# 2_POWER.net
KiCad netlist of a schematic drawn in Altium Designer
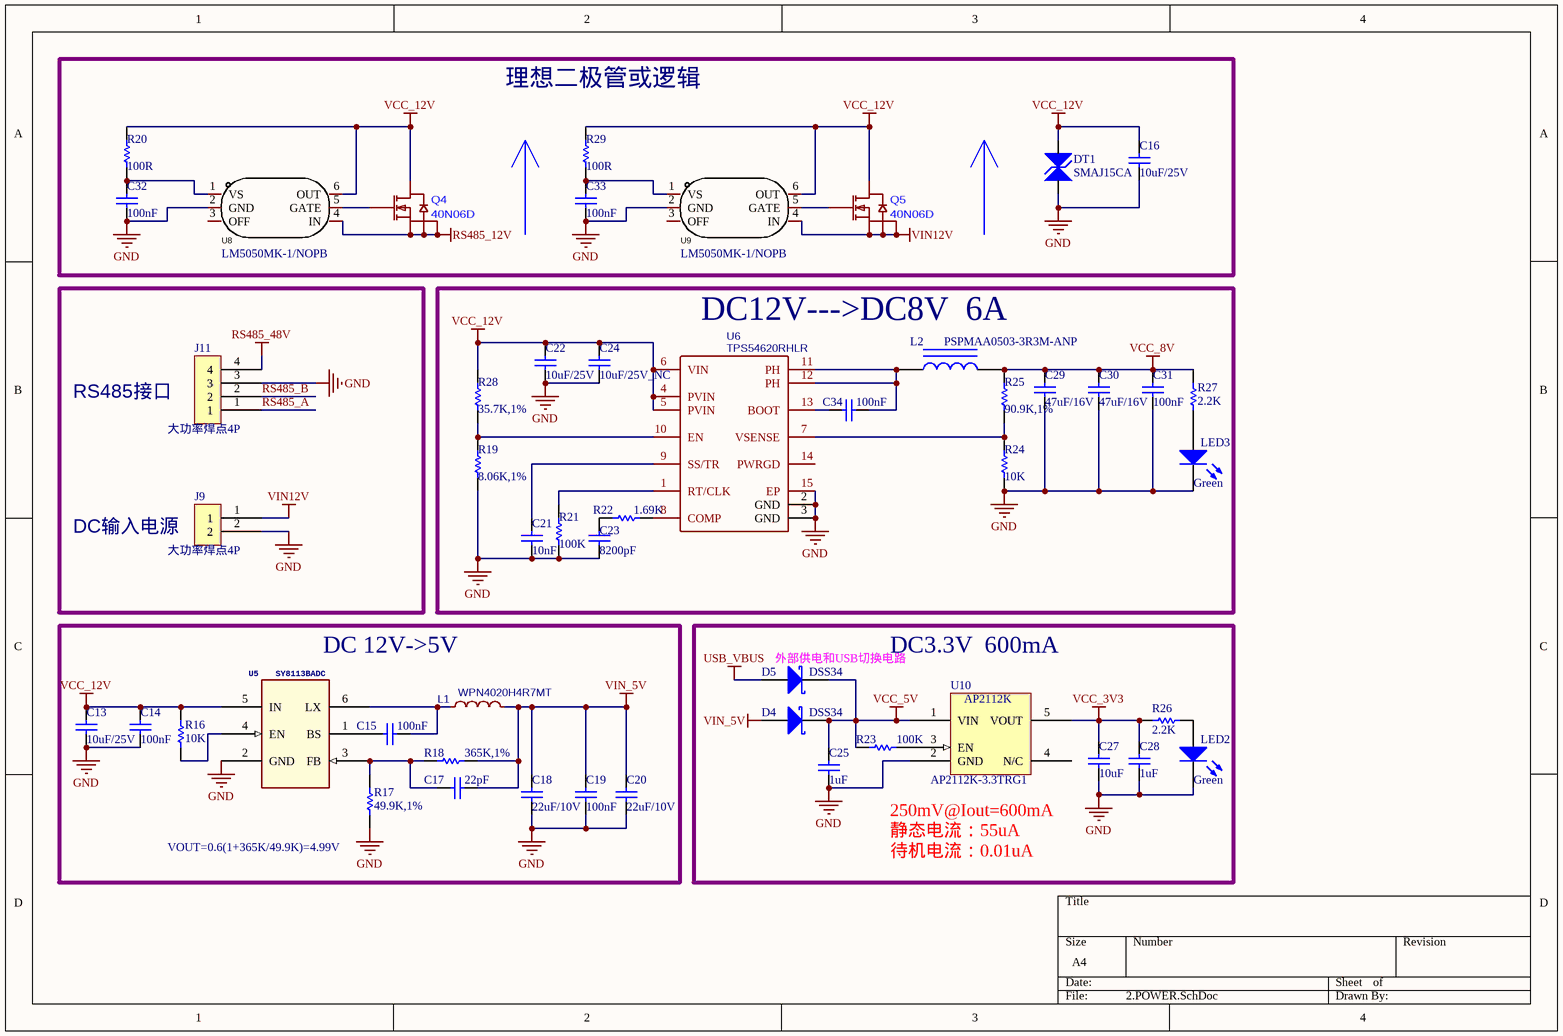
[diagram p0: 2.POWER.SchDoc]

(export (version "E")
  (design (tool "Eeschema 10.0.6"))
  (components
    (comp (ref "C13")
      (value "10uF/25V")
      (footprint "0805C")
      (description "Capacitor")
      (fields (field (name "PARTNUMBER") "CAP100NF") (field (name "PUBLISHER") "Altium Limited"))
      (libsource (lib "Miscellaneous Devices") (part "Cap"))
    )
    (comp (ref "C14")
      (value "100nF")
      (footprint "0402")
      (description "Capacitor")
      (fields (field (name "PARTNUMBER") "CAP100NF") (field (name "PUBLISHER") "Altium Limited"))
      (libsource (lib "Miscellaneous Devices") (part "Cap"))
    )
    (comp (ref "C15")
      (value "100nF")
      (footprint "0402")
      (description "Capacitor")
      (fields (field (name "PARTNUMBER") "CAP100NF") (field (name "PUBLISHER") "Altium Limited"))
      (libsource (lib "Miscellaneous Devices") (part "Cap"))
    )
    (comp (ref "C16")
      (value "10uF/25V")
      (footprint "0805C")
      (description "Capacitor")
      (fields (field (name "PARTNUMBER") "CAP100NF") (field (name "PUBLISHER") "Altium Limited"))
      (libsource (lib "Miscellaneous Devices") (part "Cap"))
    )
    (comp (ref "C17")
      (value "22pF")
      (footprint "0402")
      (description "Capacitor")
      (fields (field (name "PARTNUMBER") "CAP100NF") (field (name "PUBLISHER") "Altium Limited"))
      (libsource (lib "Miscellaneous Devices") (part "Cap"))
    )
    (comp (ref "C18")
      (value "22uF/10V")
      (footprint "0603")
      (description "Capacitor")
      (fields (field (name "PARTNUMBER") "CAP100NF") (field (name "PUBLISHER") "Altium Limited"))
      (libsource (lib "Miscellaneous Devices") (part "Cap"))
    )
    (comp (ref "C19")
      (value "100nF")
      (footprint "0402")
      (description "Capacitor")
      (fields (field (name "PARTNUMBER") "CAP100NF") (field (name "PUBLISHER") "Altium Limited"))
      (libsource (lib "Miscellaneous Devices") (part "Cap"))
    )
    (comp (ref "C20")
      (value "22uF/10V")
      (footprint "0603")
      (description "Capacitor")
      (fields (field (name "PARTNUMBER") "CAP100NF") (field (name "PUBLISHER") "Altium Limited"))
      (libsource (lib "Miscellaneous Devices") (part "Cap"))
    )
    (comp (ref "C21")
      (value "10nF")
      (footprint "0402")
      (description "Capacitor")
      (fields (field (name "PARTNUMBER") "CAP100NF") (field (name "PUBLISHER") "Altium Limited"))
      (libsource (lib "Miscellaneous Devices") (part "Cap"))
    )
    (comp (ref "C22")
      (value "10uF/25V")
      (footprint "0805C")
      (description "Capacitor")
      (fields (field (name "PARTNUMBER") "CAP100NF") (field (name "PUBLISHER") "Altium Limited"))
      (libsource (lib "Miscellaneous Devices") (part "Cap"))
    )
    (comp (ref "C23")
      (value "8200pF")
      (footprint "0402")
      (description "Capacitor")
      (fields (field (name "PARTNUMBER") "CAP100NF") (field (name "PUBLISHER") "Altium Limited"))
      (libsource (lib "Miscellaneous Devices") (part "Cap"))
    )
    (comp (ref "C24")
      (value "10uF/25V_NC")
      (footprint "0805C")
      (description "Capacitor")
      (fields (field (name "PARTNUMBER") "CAP100NF") (field (name "PUBLISHER") "Altium Limited"))
      (libsource (lib "Miscellaneous Devices") (part "Cap"))
    )
    (comp (ref "C25")
      (value "1uF")
      (footprint "0402")
      (description "Capacitor")
      (fields (field (name "PARTNUMBER") "CAP100NF") (field (name "PUBLISHER") "Altium Limited"))
      (libsource (lib "Miscellaneous Devices") (part "Cap"))
    )
    (comp (ref "C27")
      (value "10uF")
      (footprint "0402")
      (description "Capacitor")
      (fields (field (name "PARTNUMBER") "CAP100NF") (field (name "PUBLISHER") "Altium Limited"))
      (libsource (lib "Miscellaneous Devices") (part "Cap"))
    )
    (comp (ref "C28")
      (value "1uF")
      (footprint "0402")
      (description "Capacitor")
      (fields (field (name "PARTNUMBER") "CAP100NF") (field (name "PUBLISHER") "Altium Limited"))
      (libsource (lib "Miscellaneous Devices") (part "Cap"))
    )
    (comp (ref "C29")
      (value "47uF/16V")
      (footprint "1206C")
      (description "Capacitor")
      (fields (field (name "PARTNUMBER") "CAP100NF") (field (name "PUBLISHER") "Altium Limited"))
      (libsource (lib "Miscellaneous Devices") (part "Cap"))
    )
    (comp (ref "C30")
      (value "47uF/16V")
      (footprint "1206C")
      (description "Capacitor")
      (fields (field (name "PARTNUMBER") "CAP100NF") (field (name "PUBLISHER") "Altium Limited"))
      (libsource (lib "Miscellaneous Devices") (part "Cap"))
    )
    (comp (ref "C31")
      (value "100nF")
      (footprint "0402")
      (description "Capacitor")
      (fields (field (name "PARTNUMBER") "CAP100NF") (field (name "PUBLISHER") "Altium Limited"))
      (libsource (lib "Miscellaneous Devices") (part "Cap"))
    )
    (comp (ref "C32")
      (value "100nF")
      (footprint "0402")
      (description "Capacitor")
      (fields (field (name "PARTNUMBER") "CAP100NF") (field (name "PUBLISHER") "Altium Limited"))
      (libsource (lib "Miscellaneous Devices") (part "Cap"))
    )
    (comp (ref "C33")
      (value "100nF")
      (footprint "0402")
      (description "Capacitor")
      (fields (field (name "PARTNUMBER") "CAP100NF") (field (name "PUBLISHER") "Altium Limited"))
      (libsource (lib "Miscellaneous Devices") (part "Cap"))
    )
    (comp (ref "C34")
      (value "100nF")
      (footprint "0402")
      (description "Capacitor")
      (fields (field (name "PARTNUMBER") "CAP100NF") (field (name "PUBLISHER") "Altium Limited"))
      (libsource (lib "Miscellaneous Devices") (part "Cap"))
    )
    (comp (ref "D4")
      (value "DSS34")
      (footprint "SOD-123_L2.8-W1.8-LS3.7-RD")
      (description "Schottky Diode")
      (fields (field (name "PUBLISHER") "Altium Limited"))
      (libsource (lib "HM2") (part "D Schottky"))
    )
    (comp (ref "D5")
      (value "DSS34")
      (footprint "SOD-123_L2.8-W1.8-LS3.7-RD")
      (description "Schottky Diode")
      (fields (field (name "PUBLISHER") "Altium Limited"))
      (libsource (lib "HM2") (part "D Schottky"))
    )
    (comp (ref "DT1")
      (value "SMAJ15CA")
      (footprint "SMA_L4.3-W2.6-LS5.0-BI")
      (libsource (lib "Database_AD Library") (part "TVS_D"))
    )
    (comp (ref "J9") (value "大功率焊点4P") (footprint "CONN-TH_P3.5-2P") (libsource (lib "HM2") (part "SIP2")))
    (comp (ref "J11") (value "大功率焊点4P") (footprint "CONN-TH_P3.5_4P") (libsource (lib "HM2") (part "SIP4")))
    (comp (ref "L1")
      (value "WPN4020H4R7MT")
      (footprint "IND-SMD_L4.0-W4.0")
      (fields (field (name "BOM_SUPPLIER PART") "C98363"))
      (libsource (lib "IND") (part "2.2uH"))
    )
    (comp (ref "L2")
      (value "PSPMAA0503-3R3M-ANP")
      (footprint "IND-SMD_L5.4-W5.2_PSPMAA0503")
      (description "贴片电感")
      (libsource (lib "Miscellaneous Devices LC") (part "0603 3.9nH 0.3nH"))
    )
    (comp (ref "LED2")
      (value "Green")
      (footprint "LED0402")
      (description "Typical RED, GREEN, YELLOW, AMBER GaAs LED")
      (fields (field (name "PUBLISHER") "Altium Limited"))
      (libsource (lib "Miscellaneous Devices") (part "LED2"))
    )
    (comp (ref "LED3")
      (value "Green")
      (footprint "LED0402")
      (description "Typical RED, GREEN, YELLOW, AMBER GaAs LED")
      (fields (field (name "PUBLISHER") "Altium Limited"))
      (libsource (lib "Miscellaneous Devices") (part "LED2"))
    )
    (comp (ref "Q4")
      (value "40N06D")
      (footprint "WDFN-5_L3.3-W3.3-P0.65-BL")
      (libsource (lib "altium-import") (part "root_0_40N06D_"))
    )
    (comp (ref "Q5")
      (value "40N06D")
      (footprint "WDFN-5_L3.3-W3.3-P0.65-BL")
      (libsource (lib "altium-import") (part "root_0_40N06D_"))
    )
    (comp (ref "R16")
      (value "10K")
      (footprint "0402")
      (description "Resistor")
      (fields (field (name "PARTNUMBER") "RES2.2K") (field (name "PUBLISHER") "Altium Limited"))
      (libsource (lib "Miscellaneous Devices") (part "Res1"))
    )
    (comp (ref "R17")
      (value "49.9K,1%")
      (footprint "0402")
      (description "Resistor")
      (fields (field (name "PARTNUMBER") "RES2.2K") (field (name "PUBLISHER") "Altium Limited"))
      (libsource (lib "Miscellaneous Devices") (part "Res1"))
    )
    (comp (ref "R18")
      (value "365K,1%")
      (footprint "0402")
      (description "Resistor")
      (fields (field (name "PARTNUMBER") "RES2.2K") (field (name "PUBLISHER") "Altium Limited"))
      (libsource (lib "Miscellaneous Devices") (part "Res1"))
    )
    (comp (ref "R19")
      (value "8.06K,1%")
      (footprint "0402")
      (description "Resistor")
      (fields (field (name "PARTNUMBER") "RES22R") (field (name "PUBLISHER") "Altium Limited"))
      (libsource (lib "Miscellaneous Devices") (part "Res1"))
    )
    (comp (ref "R20")
      (value "100R")
      (footprint "0402")
      (description "Resistor")
      (fields (field (name "PARTNUMBER") "RES22R") (field (name "PUBLISHER") "Altium Limited"))
      (libsource (lib "Miscellaneous Devices") (part "Res1"))
    )
    (comp (ref "R21")
      (value "100K")
      (footprint "0402")
      (description "Resistor")
      (fields (field (name "PARTNUMBER") "RES22R") (field (name "PUBLISHER") "Altium Limited"))
      (libsource (lib "Miscellaneous Devices") (part "Res1"))
    )
    (comp (ref "R22")
      (value "1.69K")
      (footprint "0402")
      (description "Resistor")
      (fields (field (name "PARTNUMBER") "RES22R") (field (name "PUBLISHER") "Altium Limited"))
      (libsource (lib "Miscellaneous Devices") (part "Res1"))
    )
    (comp (ref "R23")
      (value "100K")
      (footprint "0402")
      (description "Resistor")
      (fields (field (name "PARTNUMBER") "RES22R") (field (name "PUBLISHER") "Altium Limited"))
      (libsource (lib "Miscellaneous Devices") (part "Res1"))
    )
    (comp (ref "R24")
      (value "10K")
      (footprint "0402")
      (description "Resistor")
      (fields (field (name "PARTNUMBER") "RES22R") (field (name "PUBLISHER") "Altium Limited"))
      (libsource (lib "Miscellaneous Devices") (part "Res1"))
    )
    (comp (ref "R25")
      (value "90.9K,1%")
      (footprint "0402")
      (description "Resistor")
      (fields (field (name "PARTNUMBER") "RES22R") (field (name "PUBLISHER") "Altium Limited"))
      (libsource (lib "Miscellaneous Devices") (part "Res1"))
    )
    (comp (ref "R26")
      (value "2.2K")
      (footprint "0402")
      (description "Resistor")
      (fields (field (name "PARTNUMBER") "RES2.2K") (field (name "PUBLISHER") "Altium Limited"))
      (libsource (lib "Miscellaneous Devices") (part "Res1"))
    )
    (comp (ref "R27")
      (value "2.2K")
      (footprint "0402")
      (description "Resistor")
      (fields (field (name "PARTNUMBER") "RES22.1K") (field (name "PUBLISHER") "Altium Limited"))
      (libsource (lib "Miscellaneous Devices") (part "Res1"))
    )
    (comp (ref "R28")
      (value "35.7K,1%")
      (footprint "0402")
      (description "Resistor")
      (fields (field (name "PARTNUMBER") "RES22R") (field (name "PUBLISHER") "Altium Limited"))
      (libsource (lib "Miscellaneous Devices") (part "Res1"))
    )
    (comp (ref "R29")
      (value "100R")
      (footprint "0402")
      (description "Resistor")
      (fields (field (name "PARTNUMBER") "RES22R") (field (name "PUBLISHER") "Altium Limited"))
      (libsource (lib "Miscellaneous Devices") (part "Res1"))
    )
    (comp (ref "U5") (value "SY8113BADC") (footprint "SOT23-6") (libsource (lib "*") (part "SY81XX")))
    (comp (ref "U6")
      (value "TPS54620RHLR")
      (footprint "VQFN-14_L3.5-W3.5-P0.50-TL-EP_TPS54622RHLT")
      (fields (field (name "BOM_SUPPLIER PART") "C263274") (field (name "CONTRIBUTOR") "LCSC"))
      (libsource (lib "altium-import") (part "root_0_TPS54620RHLR_"))
    )
    (comp (ref "U8")
      (value "LM5050MK-1/NOPB")
      (footprint "TSOT-23-6_L2.9-W1.6-P0.95-LS2.8-BR")
      (fields (field (name "DESIGNER") "U?"))
      (libsource (lib "HM2") (part "LM5050MK-1/NOPB"))
    )
    (comp (ref "U9")
      (value "LM5050MK-1/NOPB")
      (footprint "TSOT-23-6_L2.9-W1.6-P0.95-LS2.8-BR")
      (fields (field (name "DESIGNER") "U?"))
      (libsource (lib "HM2") (part "LM5050MK-1/NOPB"))
    )
    (comp (ref "U10") (value "AP2112K-3.3TRG1") (footprint "SOT23-5") (libsource (lib "HM2") (part "AP2112")))
  )
  (nets
    (net (code "1") (name "/RS485_A") (class "Default")
      (node (ref "J11") (pin "1") (pinfunction "1_1") (pintype "passive"))
    )
    (net (code "2") (name "/RS485_B") (class "Default")
      (node (ref "J11") (pin "2") (pinfunction "2_2") (pintype "passive"))
    )
    (net (code "3") (name "GND") (class "Default")
      (node (ref "C13") (pin "2") (pinfunction "2_2") (pintype "passive"))
      (node (ref "C14") (pin "1") (pinfunction "1_1") (pintype "passive"))
      (node (ref "C16") (pin "2") (pinfunction "2_2") (pintype "passive"))
      (node (ref "C18") (pin "2") (pinfunction "2_2") (pintype "passive"))
      (node (ref "C19") (pin "2") (pinfunction "2_2") (pintype "passive"))
      (node (ref "C20") (pin "2") (pinfunction "2_2") (pintype "passive"))
      (node (ref "C21") (pin "1") (pinfunction "1_1") (pintype "passive"))
      (node (ref "C22") (pin "2") (pinfunction "2_2") (pintype "passive"))
      (node (ref "C23") (pin "1") (pinfunction "1_1") (pintype "passive"))
      (node (ref "C24") (pin "2") (pinfunction "2_2") (pintype "passive"))
      (node (ref "C25") (pin "2") (pinfunction "2_2") (pintype "passive"))
      (node (ref "C27") (pin "1") (pinfunction "1_1") (pintype "passive"))
      (node (ref "C28") (pin "1") (pinfunction "1_1") (pintype "passive"))
      (node (ref "C29") (pin "2") (pinfunction "2_2") (pintype "passive"))
      (node (ref "C30") (pin "2") (pinfunction "2_2") (pintype "passive"))
      (node (ref "C31") (pin "1") (pinfunction "1_1") (pintype "passive"))
      (node (ref "C32") (pin "1") (pinfunction "1_1") (pintype "passive"))
      (node (ref "C33") (pin "1") (pinfunction "1_1") (pintype "passive"))
      (node (ref "DT1") (pin "1") (pinfunction "1_1") (pintype "passive"))
      (node (ref "J11") (pin "3") (pinfunction "3_3") (pintype "passive"))
      (node (ref "J9") (pin "2") (pinfunction "2_2") (pintype "passive"))
      (node (ref "LED2") (pin "2") (pinfunction "K_2") (pintype "passive"))
      (node (ref "LED3") (pin "2") (pinfunction "K_2") (pintype "passive"))
      (node (ref "R17") (pin "2") (pinfunction "2_2") (pintype "passive"))
      (node (ref "R19") (pin "2") (pinfunction "2_2") (pintype "passive"))
      (node (ref "R21") (pin "2") (pinfunction "2_2") (pintype "passive"))
      (node (ref "R24") (pin "2") (pinfunction "2_2") (pintype "passive"))
      (node (ref "U10") (pin "2") (pinfunction "GND_2") (pintype "passive"))
      (node (ref "U5") (pin "2") (pinfunction "GND_2") (pintype "power_in"))
      (node (ref "U6") (pin "15") (pinfunction "EP_15") (pintype "passive"))
      (node (ref "U6") (pin "2") (pinfunction "GND_2") (pintype "passive"))
      (node (ref "U6") (pin "3") (pinfunction "GND_3") (pintype "passive"))
      (node (ref "U8") (pin "2") (pinfunction "GND_2") (pintype "passive"))
      (node (ref "U9") (pin "2") (pinfunction "GND_2") (pintype "passive"))
    )
    (net (code "4") (name "Net-(C23-Pad2)") (class "Default")
      (node (ref "C23") (pin "2") (pinfunction "2_2") (pintype "passive"))
      (node (ref "R22") (pin "1") (pinfunction "1_1") (pintype "passive"))
    )
    (net (code "5") (name "Net-(C34-Pad2)") (class "Default")
      (node (ref "C34") (pin "2") (pinfunction "2_2") (pintype "passive"))
      (node (ref "L2") (pin "1") (pinfunction "1_1") (pintype "passive"))
      (node (ref "U6") (pin "11") (pinfunction "PH_11") (pintype "passive"))
      (node (ref "U6") (pin "12") (pinfunction "PH_12") (pintype "passive"))
    )
    (net (code "6") (name "Net-(LED2-A)") (class "Default")
      (node (ref "LED2") (pin "1") (pinfunction "A_1") (pintype "passive"))
      (node (ref "R26") (pin "1") (pinfunction "1_1") (pintype "passive"))
    )
    (net (code "7") (name "Net-(LED3-A)") (class "Default")
      (node (ref "LED3") (pin "1") (pinfunction "A_1") (pintype "passive"))
      (node (ref "R27") (pin "1") (pinfunction "1_1") (pintype "passive"))
    )
    (net (code "8") (name "Net-(Q4-G)") (class "Default")
      (node (ref "Q4") (pin "4") (pinfunction "G_4") (pintype "passive"))
      (node (ref "U8") (pin "5") (pinfunction "GATE_5") (pintype "passive"))
    )
    (net (code "9") (name "Net-(Q5-G)") (class "Default")
      (node (ref "Q5") (pin "4") (pinfunction "G_4") (pintype "passive"))
      (node (ref "U9") (pin "5") (pinfunction "GATE_5") (pintype "passive"))
    )
    (net (code "10") (name "Net-(U5-BS)") (class "Default")
      (node (ref "C15") (pin "2") (pinfunction "2_2") (pintype "passive"))
      (node (ref "U5") (pin "1") (pinfunction "BS_1") (pintype "passive"))
    )
    (net (code "11") (name "Net-(U5-EN)") (class "Default")
      (node (ref "R16") (pin "1") (pinfunction "1_1") (pintype "passive"))
      (node (ref "U5") (pin "4") (pinfunction "EN_4") (pintype "input"))
    )
    (net (code "12") (name "Net-(U5-FB)") (class "Default")
      (node (ref "C17") (pin "2") (pinfunction "2_2") (pintype "passive"))
      (node (ref "R17") (pin "1") (pinfunction "1_1") (pintype "passive"))
      (node (ref "R18") (pin "2") (pinfunction "2_2") (pintype "passive"))
      (node (ref "U5") (pin "3") (pinfunction "FB_3") (pintype "input"))
    )
    (net (code "13") (name "Net-(U5-LX)") (class "Default")
      (node (ref "C15") (pin "1") (pinfunction "1_1") (pintype "passive"))
      (node (ref "L1") (pin "1") (pinfunction "1_1") (pintype "passive"))
      (node (ref "U5") (pin "6") (pinfunction "LX_6") (pintype "passive"))
    )
    (net (code "14") (name "Net-(U6-BOOT)") (class "Default")
      (node (ref "C34") (pin "1") (pinfunction "1_1") (pintype "passive"))
      (node (ref "U6") (pin "13") (pinfunction "BOOT_13") (pintype "passive"))
    )
    (net (code "15") (name "Net-(U6-COMP)") (class "Default")
      (node (ref "R22") (pin "2") (pinfunction "2_2") (pintype "passive"))
      (node (ref "U6") (pin "8") (pinfunction "COMP_8") (pintype "passive"))
    )
    (net (code "16") (name "Net-(U6-EN)") (class "Default")
      (node (ref "R19") (pin "1") (pinfunction "1_1") (pintype "passive"))
      (node (ref "R28") (pin "2") (pinfunction "2_2") (pintype "passive"))
      (node (ref "U6") (pin "10") (pinfunction "EN_10") (pintype "passive"))
    )
    (net (code "17") (name "Net-(U6-RT{slash}CLK)") (class "Default")
      (node (ref "R21") (pin "1") (pinfunction "1_1") (pintype "passive"))
      (node (ref "U6") (pin "1") (pinfunction "RT/CLK_1") (pintype "passive"))
    )
    (net (code "18") (name "Net-(U6-SS{slash}TR)") (class "Default")
      (node (ref "C21") (pin "2") (pinfunction "2_2") (pintype "passive"))
      (node (ref "U6") (pin "9") (pinfunction "SS/TR_9") (pintype "passive"))
    )
    (net (code "19") (name "Net-(U6-VSENSE)") (class "Default")
      (node (ref "R24") (pin "1") (pinfunction "1_1") (pintype "passive"))
      (node (ref "R25") (pin "2") (pinfunction "2_2") (pintype "passive"))
      (node (ref "U6") (pin "7") (pinfunction "VSENSE_7") (pintype "passive"))
    )
    (net (code "20") (name "Net-(U8-VS)") (class "Default")
      (node (ref "C32") (pin "2") (pinfunction "2_2") (pintype "passive"))
      (node (ref "R20") (pin "2") (pinfunction "2_2") (pintype "passive"))
      (node (ref "U8") (pin "1") (pinfunction "VS_1") (pintype "passive"))
    )
    (net (code "21") (name "Net-(U9-VS)") (class "Default")
      (node (ref "C33") (pin "2") (pinfunction "2_2") (pintype "passive"))
      (node (ref "R29") (pin "2") (pinfunction "2_2") (pintype "passive"))
      (node (ref "U9") (pin "1") (pinfunction "VS_1") (pintype "passive"))
    )
    (net (code "22") (name "Net-(U10-EN)") (class "Default")
      (node (ref "R23") (pin "2") (pinfunction "2_2") (pintype "passive"))
      (node (ref "U10") (pin "3") (pinfunction "EN_3") (pintype "input"))
    )
    (net (code "23") (name "RS485_12V") (class "Default")
      (node (ref "Q4") (pin "1") (pinfunction "S_1") (pintype "passive"))
      (node (ref "Q4") (pin "2") (pinfunction "S_2") (pintype "passive"))
      (node (ref "Q4") (pin "3") (pinfunction "S_3") (pintype "passive"))
      (node (ref "U8") (pin "4") (pinfunction "IN_4") (pintype "passive"))
    )
    (net (code "24") (name "RS485_48V") (class "Default")
      (node (ref "J11") (pin "4") (pinfunction "4_4") (pintype "passive"))
    )
    (net (code "25") (name "USB_VBUS") (class "Default")
      (node (ref "D5") (pin "1") (pinfunction "A_1") (pintype "passive"))
    )
    (net (code "26") (name "VCC_3V3") (class "Default")
      (node (ref "C27") (pin "2") (pinfunction "2_2") (pintype "passive"))
      (node (ref "C28") (pin "2") (pinfunction "2_2") (pintype "passive"))
      (node (ref "R26") (pin "2") (pinfunction "2_2") (pintype "passive"))
      (node (ref "U10") (pin "5") (pinfunction "VOUT_5") (pintype "power_in"))
    )
    (net (code "27") (name "VCC_5V") (class "Default")
      (node (ref "C25") (pin "1") (pinfunction "1_1") (pintype "passive"))
      (node (ref "D4") (pin "2") (pinfunction "K_2") (pintype "passive"))
      (node (ref "D5") (pin "2") (pinfunction "K_2") (pintype "passive"))
      (node (ref "R23") (pin "1") (pinfunction "1_1") (pintype "passive"))
      (node (ref "U10") (pin "1") (pinfunction "VIN_1") (pintype "power_in"))
    )
    (net (code "28") (name "VCC_8V") (class "Default")
      (node (ref "C29") (pin "1") (pinfunction "1_1") (pintype "passive"))
      (node (ref "C30") (pin "1") (pinfunction "1_1") (pintype "passive"))
      (node (ref "C31") (pin "2") (pinfunction "2_2") (pintype "passive"))
      (node (ref "L2") (pin "2") (pinfunction "2_2") (pintype "passive"))
      (node (ref "R25") (pin "1") (pinfunction "1_1") (pintype "passive"))
      (node (ref "R27") (pin "2") (pinfunction "2_2") (pintype "passive"))
    )
    (net (code "29") (name "VCC_12V") (class "Default")
      (node (ref "C13") (pin "1") (pinfunction "1_1") (pintype "passive"))
      (node (ref "C14") (pin "2") (pinfunction "2_2") (pintype "passive"))
      (node (ref "C16") (pin "1") (pinfunction "1_1") (pintype "passive"))
      (node (ref "C22") (pin "1") (pinfunction "1_1") (pintype "passive"))
      (node (ref "C24") (pin "1") (pinfunction "1_1") (pintype "passive"))
      (node (ref "DT1") (pin "2") (pinfunction "2_2") (pintype "passive"))
      (node (ref "Q4") (pin "5") (pinfunction "D_5") (pintype "passive"))
      (node (ref "Q5") (pin "5") (pinfunction "D_5") (pintype "passive"))
      (node (ref "R16") (pin "2") (pinfunction "2_2") (pintype "passive"))
      (node (ref "R20") (pin "1") (pinfunction "1_1") (pintype "passive"))
      (node (ref "R28") (pin "1") (pinfunction "1_1") (pintype "passive"))
      (node (ref "R29") (pin "1") (pinfunction "1_1") (pintype "passive"))
      (node (ref "U5") (pin "5") (pinfunction "IN_5") (pintype "power_in"))
      (node (ref "U6") (pin "4") (pinfunction "PVIN_4") (pintype "passive"))
      (node (ref "U6") (pin "5") (pinfunction "PVIN_5") (pintype "passive"))
      (node (ref "U6") (pin "6") (pinfunction "VIN_6") (pintype "passive"))
      (node (ref "U8") (pin "6") (pinfunction "OUT_6") (pintype "passive"))
      (node (ref "U9") (pin "6") (pinfunction "OUT_6") (pintype "passive"))
    )
    (net (code "30") (name "VIN12V") (class "Default")
      (node (ref "J9") (pin "1") (pinfunction "1_1") (pintype "passive"))
      (node (ref "Q5") (pin "1") (pinfunction "S_1") (pintype "passive"))
      (node (ref "Q5") (pin "2") (pinfunction "S_2") (pintype "passive"))
      (node (ref "Q5") (pin "3") (pinfunction "S_3") (pintype "passive"))
      (node (ref "U9") (pin "4") (pinfunction "IN_4") (pintype "passive"))
    )
    (net (code "31") (name "VIN_5V") (class "Default")
      (node (ref "C17") (pin "1") (pinfunction "1_1") (pintype "passive"))
      (node (ref "C18") (pin "1") (pinfunction "1_1") (pintype "passive"))
      (node (ref "C19") (pin "1") (pinfunction "1_1") (pintype "passive"))
      (node (ref "C20") (pin "1") (pinfunction "1_1") (pintype "passive"))
      (node (ref "D4") (pin "1") (pinfunction "A_1") (pintype "passive"))
      (node (ref "L1") (pin "2") (pinfunction "2_2") (pintype "passive"))
      (node (ref "R18") (pin "1") (pinfunction "1_1") (pintype "passive"))
    )
    (net (code "32") (name "unconnected-(U6-PWRGD-Pad14)") (class "Default")
      (node (ref "U6") (pin "14") (pinfunction "PWRGD_14") (pintype "passive"))
    )
    (net (code "33") (name "unconnected-(U8-OFF-Pad3)") (class "Default")
      (node (ref "U8") (pin "3") (pinfunction "OFF_3") (pintype "passive"))
    )
    (net (code "34") (name "unconnected-(U9-OFF-Pad3)") (class "Default")
      (node (ref "U9") (pin "3") (pinfunction "OFF_3") (pintype "passive"))
    )
    (net (code "35") (name "unconnected-(U10-N{slash}C-Pad4)") (class "Default")
      (node (ref "U10") (pin "4") (pinfunction "N/C_4") (pintype "passive"))
    )
  )
)
